# LiPo_charger.net
KiCad netlist of a schematic drawn in Altium Designer
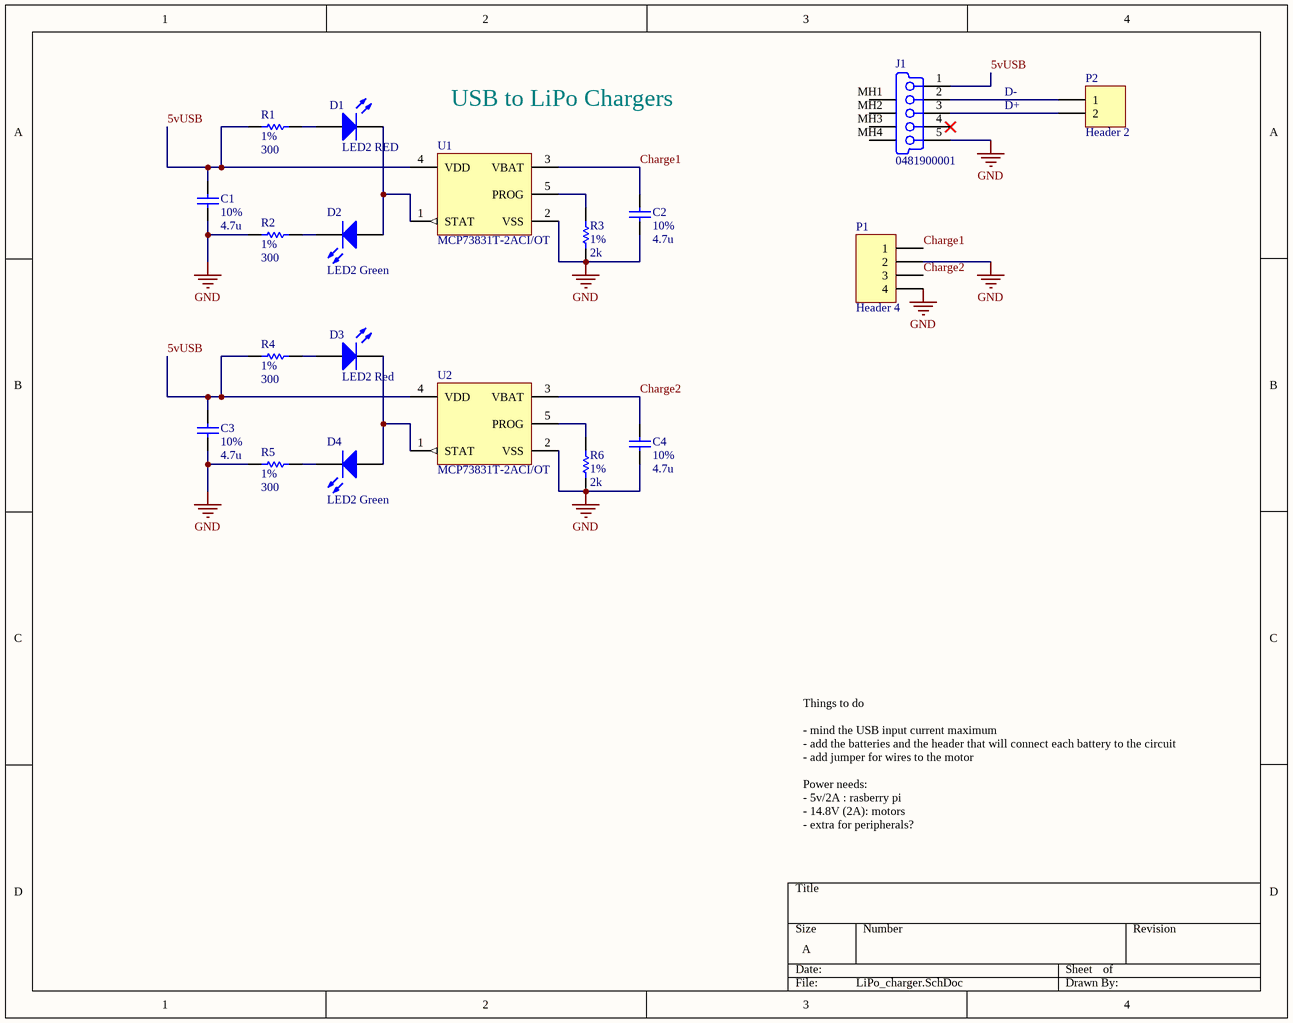
[diagram p0: LiPo_charger.SchDoc]

(export (version "E")
  (design (tool "Eeschema 10.0.6"))
  (components
    (comp (ref "C1")
      (value "10%")
      (footprint "6-0805_M")
      (description "Capacitor")
      (fields (field (name "ALTIUM_VALUE") "4.7u") (field (name "PUBLISHER") "Altium Limited"))
      (libsource (lib "Miscellaneous Devices") (part "Cap"))
    )
    (comp (ref "C2")
      (value "10%")
      (footprint "6-0805_M")
      (description "Capacitor")
      (fields (field (name "ALTIUM_VALUE") "4.7u") (field (name "PUBLISHER") "Altium Limited"))
      (libsource (lib "Miscellaneous Devices") (part "Cap"))
    )
    (comp (ref "C3")
      (value "10%")
      (footprint "6-0805_M")
      (description "Capacitor")
      (fields (field (name "ALTIUM_VALUE") "4.7u") (field (name "PUBLISHER") "Altium Limited"))
      (libsource (lib "Miscellaneous Devices") (part "Cap"))
    )
    (comp (ref "C4")
      (value "10%")
      (footprint "6-0805_M")
      (description "Capacitor")
      (fields (field (name "ALTIUM_VALUE") "4.7u") (field (name "PUBLISHER") "Altium Limited"))
      (libsource (lib "Miscellaneous Devices") (part "Cap"))
    )
    (comp (ref "D1")
      (value "LED2 RED")
      (footprint "3.2X1.6X1.1")
      (description "Typical RED, GREEN, YELLOW, AMBER GaAs LED")
      (fields (field (name "PUBLISHER") "Altium Limited"))
      (libsource (lib "Miscellaneous Devices") (part "LED2"))
    )
    (comp (ref "D2")
      (value "LED2 Green")
      (footprint "3.2X1.6X1.1")
      (description "Typical RED, GREEN, YELLOW, AMBER GaAs LED")
      (fields (field (name "PUBLISHER") "Altium Limited"))
      (libsource (lib "Miscellaneous Devices") (part "LED2"))
    )
    (comp (ref "D3")
      (value "LED2 Red")
      (footprint "3.2X1.6X1.1")
      (description "Typical RED, GREEN, YELLOW, AMBER GaAs LED")
      (fields (field (name "PUBLISHER") "Altium Limited"))
      (libsource (lib "Miscellaneous Devices") (part "LED2"))
    )
    (comp (ref "D4")
      (value "LED2 Green")
      (footprint "3.2X1.6X1.1")
      (description "Typical RED, GREEN, YELLOW, AMBER GaAs LED")
      (fields (field (name "PUBLISHER") "Altium Limited"))
      (libsource (lib "Miscellaneous Devices") (part "LED2"))
    )
    (comp (ref "J1")
      (value "0481900001")
      (footprint "481900001")
      (fields (field (name "PUBLISHER") "Altium Limited"))
      (libsource (lib "Molex Serial Bus Mini USB") (part "0481900001"))
    )
    (comp (ref "P1")
      (value "Header 4")
      (footprint "HDR1X4")
      (description "Header, 4-Pin")
      (fields (field (name "PUBLISHER") "Altium Limited"))
      (libsource (lib "Miscellaneous Connectors") (part "Header 4"))
    )
    (comp (ref "P2")
      (value "Header 2")
      (footprint "HDR1X2")
      (description "Header, 2-Pin")
      (fields (field (name "PUBLISHER") "Altium Limited"))
      (libsource (lib "Miscellaneous Connectors") (part "Header 2"))
    )
    (comp (ref "R1")
      (value "1%")
      (footprint "6-0805_M")
      (description "Resistor")
      (fields (field (name "ALTIUM_VALUE") "300") (field (name "PUBLISHER") "Altium Limited"))
      (libsource (lib "Miscellaneous Devices") (part "Res1"))
    )
    (comp (ref "R2")
      (value "1%")
      (footprint "6-0805_M")
      (description "Resistor")
      (fields (field (name "ALTIUM_VALUE") "300") (field (name "PUBLISHER") "Altium Limited"))
      (libsource (lib "Miscellaneous Devices") (part "Res1"))
    )
    (comp (ref "R3")
      (value "1%")
      (footprint "6-0805_M")
      (description "Resistor")
      (fields (field (name "ALTIUM_VALUE") "2k") (field (name "PUBLISHER") "Altium Limited"))
      (libsource (lib "Miscellaneous Devices") (part "Res1"))
    )
    (comp (ref "R4")
      (value "1%")
      (footprint "6-0805_M")
      (description "Resistor")
      (fields (field (name "ALTIUM_VALUE") "300") (field (name "PUBLISHER") "Altium Limited"))
      (libsource (lib "Miscellaneous Devices") (part "Res1"))
    )
    (comp (ref "R5")
      (value "1%")
      (footprint "6-0805_M")
      (description "Resistor")
      (fields (field (name "ALTIUM_VALUE") "300") (field (name "PUBLISHER") "Altium Limited"))
      (libsource (lib "Miscellaneous Devices") (part "Res1"))
    )
    (comp (ref "R6")
      (value "1%")
      (footprint "6-0805_M")
      (description "Resistor")
      (fields (field (name "ALTIUM_VALUE") "2k") (field (name "PUBLISHER") "Altium Limited"))
      (libsource (lib "Miscellaneous Devices") (part "Res1"))
    )
    (comp (ref "U1")
      (value "MCP73831T-2ACI/OT")
      (footprint "SOT-23-OT5_N")
      (fields (field (name "PUBLISHER") "Altium Limited"))
      (libsource (lib "Microchip Power Mgt Battery Management") (part "MCP73831T-2ACI/OT"))
    )
    (comp (ref "U2")
      (value "MCP73831T-2ACI/OT")
      (footprint "SOT-23-OT5_N")
      (fields (field (name "PUBLISHER") "Altium Limited"))
      (libsource (lib "Microchip Power Mgt Battery Management") (part "MCP73831T-2ACI/OT"))
    )
  )
  (nets
    (net (code "1") (name "/5vUSB") (class "Default")
      (node (ref "C1") (pin "2") (pinfunction "2_2") (pintype "passive"))
      (node (ref "C3") (pin "2") (pinfunction "2_2") (pintype "passive"))
      (node (ref "J1") (pin "1") (pinfunction "V_BUS_(5V)_1") (pintype "passive"))
      (node (ref "R1") (pin "1") (pinfunction "1_1") (pintype "passive"))
      (node (ref "R4") (pin "1") (pinfunction "1_1") (pintype "passive"))
      (node (ref "U1") (pin "4") (pinfunction "VDD_4") (pintype "power_in"))
      (node (ref "U2") (pin "4") (pinfunction "VDD_4") (pintype "power_in"))
    )
    (net (code "2") (name "/Charge1") (class "Default")
      (node (ref "C2") (pin "2") (pinfunction "2_2") (pintype "passive"))
      (node (ref "P1") (pin "1") (pinfunction "1_1") (pintype "passive"))
      (node (ref "U1") (pin "3") (pinfunction "VBAT_3") (pintype "power_in"))
    )
    (net (code "3") (name "/Charge2") (class "Default")
      (node (ref "C4") (pin "2") (pinfunction "2_2") (pintype "passive"))
      (node (ref "P1") (pin "3") (pinfunction "3_3") (pintype "passive"))
      (node (ref "U2") (pin "3") (pinfunction "VBAT_3") (pintype "power_in"))
    )
    (net (code "4") (name "GND") (class "Default")
      (node (ref "C1") (pin "1") (pinfunction "1_1") (pintype "passive"))
      (node (ref "C2") (pin "1") (pinfunction "1_1") (pintype "passive"))
      (node (ref "C3") (pin "1") (pinfunction "1_1") (pintype "passive"))
      (node (ref "C4") (pin "1") (pinfunction "1_1") (pintype "passive"))
      (node (ref "J1") (pin "5") (pinfunction "GND_5") (pintype "passive"))
      (node (ref "P1") (pin "2") (pinfunction "2_2") (pintype "passive"))
      (node (ref "P1") (pin "4") (pinfunction "4_4") (pintype "passive"))
      (node (ref "R2") (pin "1") (pinfunction "1_1") (pintype "passive"))
      (node (ref "R3") (pin "1") (pinfunction "1_1") (pintype "passive"))
      (node (ref "R5") (pin "1") (pinfunction "1_1") (pintype "passive"))
      (node (ref "R6") (pin "1") (pinfunction "1_1") (pintype "passive"))
      (node (ref "U1") (pin "2") (pinfunction "VSS_2") (pintype "power_in"))
      (node (ref "U2") (pin "2") (pinfunction "VSS_2") (pintype "power_in"))
    )
    (net (code "5") (name "Net-(D1-A)") (class "Default")
      (node (ref "D1") (pin "1") (pinfunction "A_1") (pintype "passive"))
      (node (ref "R1") (pin "2") (pinfunction "2_2") (pintype "passive"))
    )
    (net (code "6") (name "Net-(D1-K)") (class "Default")
      (node (ref "D1") (pin "2") (pinfunction "K_2") (pintype "passive"))
      (node (ref "D2") (pin "1") (pinfunction "A_1") (pintype "passive"))
      (node (ref "U1") (pin "1") (pinfunction "STAT_1") (pintype "output"))
    )
    (net (code "7") (name "Net-(D2-K)") (class "Default")
      (node (ref "D2") (pin "2") (pinfunction "K_2") (pintype "passive"))
      (node (ref "R2") (pin "2") (pinfunction "2_2") (pintype "passive"))
    )
    (net (code "8") (name "Net-(D3-A)") (class "Default")
      (node (ref "D3") (pin "1") (pinfunction "A_1") (pintype "passive"))
      (node (ref "R4") (pin "2") (pinfunction "2_2") (pintype "passive"))
    )
    (net (code "9") (name "Net-(D3-K)") (class "Default")
      (node (ref "D3") (pin "2") (pinfunction "K_2") (pintype "passive"))
      (node (ref "D4") (pin "1") (pinfunction "A_1") (pintype "passive"))
      (node (ref "U2") (pin "1") (pinfunction "STAT_1") (pintype "output"))
    )
    (net (code "10") (name "Net-(D4-K)") (class "Default")
      (node (ref "D4") (pin "2") (pinfunction "K_2") (pintype "passive"))
      (node (ref "R5") (pin "2") (pinfunction "2_2") (pintype "passive"))
    )
    (net (code "11") (name "Net-(J1-D+)") (class "Default")
      (node (ref "J1") (pin "3") (pinfunction "D+_3") (pintype "passive"))
      (node (ref "P2") (pin "2") (pinfunction "2_2") (pintype "passive"))
    )
    (net (code "12") (name "Net-(J1-D-)") (class "Default")
      (node (ref "J1") (pin "2") (pinfunction "D-_2") (pintype "passive"))
      (node (ref "P2") (pin "1") (pinfunction "1_1") (pintype "passive"))
    )
    (net (code "13") (name "Net-(U1-PROG)") (class "Default")
      (node (ref "R3") (pin "2") (pinfunction "2_2") (pintype "passive"))
      (node (ref "U1") (pin "5") (pinfunction "PROG_5") (pintype "passive"))
    )
    (net (code "14") (name "Net-(U2-PROG)") (class "Default")
      (node (ref "R6") (pin "2") (pinfunction "2_2") (pintype "passive"))
      (node (ref "U2") (pin "5") (pinfunction "PROG_5") (pintype "passive"))
    )
    (net (code "15") (name "unconnected-(J1-NC-Pad4)") (class "Default")
      (node (ref "J1") (pin "4") (pinfunction "NC_4") (pintype "passive+no_connect"))
    )
    (net (code "16") (name "unconnected-(J1-Tab-PadMH1)") (class "Default")
      (node (ref "J1") (pin "MH1") (pinfunction "Tab_MH1") (pintype "passive"))
    )
    (net (code "17") (name "unconnected-(J1-Tab-PadMH2)") (class "Default")
      (node (ref "J1") (pin "MH2") (pinfunction "Tab_MH2") (pintype "passive"))
    )
    (net (code "18") (name "unconnected-(J1-Tab-PadMH3)") (class "Default")
      (node (ref "J1") (pin "MH3") (pinfunction "Tab_MH3") (pintype "passive"))
    )
    (net (code "19") (name "unconnected-(J1-Tab-PadMH4)") (class "Default")
      (node (ref "J1") (pin "MH4") (pinfunction "Tab_MH4") (pintype "passive"))
    )
  )
)
